# Reference_voltage.net
KiCad netlist of a schematic drawn in Altium Designer
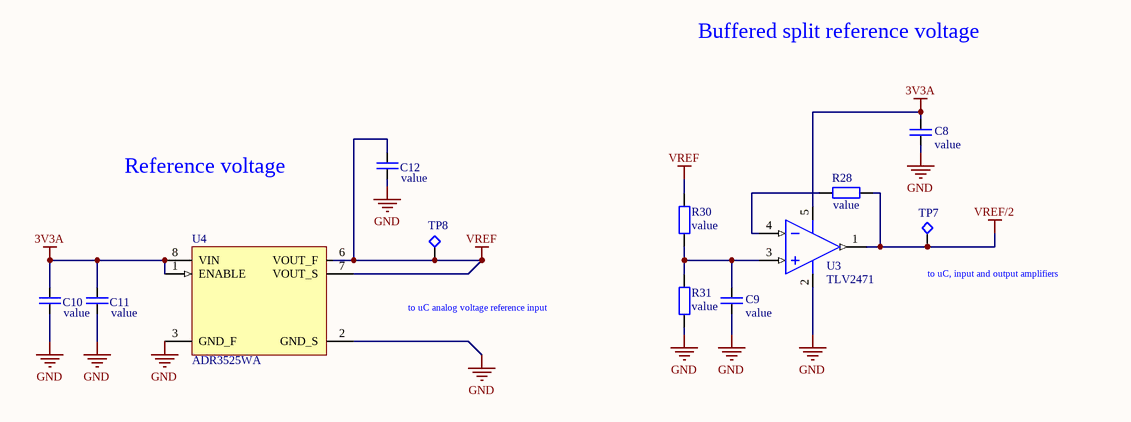
[diagram p0: Reference_voltage.SchDoc]

(export (version "E")
  (design (tool "Eeschema 10.0.6"))
  (components
    (comp (ref "C8")
      (value "value")
      (footprint "C_0603")
      (description "Generic capacitor")
      (fields (field (name "Comment") "comment"))
      (libsource (lib "DAQ") (part "Capacitor"))
    )
    (comp (ref "C9")
      (value "value")
      (footprint "C_0603")
      (description "Generic capacitor")
      (fields (field (name "Comment") "comment"))
      (libsource (lib "DAQ") (part "Capacitor"))
    )
    (comp (ref "C10")
      (value "value")
      (footprint "C_0603")
      (description "Generic capacitor")
      (fields (field (name "Comment") "comment"))
      (libsource (lib "DAQ") (part "Capacitor"))
    )
    (comp (ref "C11")
      (value "value")
      (footprint "C_0603")
      (description "Generic capacitor")
      (fields (field (name "Comment") "comment"))
      (libsource (lib "DAQ") (part "Capacitor"))
    )
    (comp (ref "C12")
      (value "value")
      (footprint "C_0603")
      (description "Generic capacitor")
      (fields (field (name "Comment") "comment"))
      (libsource (lib "DAQ") (part "Capacitor"))
    )
    (comp (ref "R28")
      (value "value")
      (footprint "R_0603")
      (description "Generic resistor")
      (fields (field (name "Comment") "comment"))
      (libsource (lib "DAQ") (part "Resistor"))
    )
    (comp (ref "R30")
      (value "value")
      (footprint "R_0603")
      (description "Generic resistor")
      (fields (field (name "Comment") "comment"))
      (libsource (lib "DAQ") (part "Resistor"))
    )
    (comp (ref "R31")
      (value "value")
      (footprint "R_0603")
      (description "Generic resistor")
      (fields (field (name "Comment") "comment"))
      (libsource (lib "DAQ") (part "Resistor"))
    )
    (comp (ref "TP7")
      (value "test point 1.5mm")
      (footprint "TP1_FULL")
      (description "Test point ,1.5mm diameter, no hole")
      (libsource (lib "DAQ") (part "Test Point"))
    )
    (comp (ref "TP8")
      (value "test point 1.5mm")
      (footprint "TP1_FULL")
      (description "Test point ,1.5mm diameter, no hole")
      (libsource (lib "DAQ") (part "Test Point"))
    )
    (comp (ref "U3")
      (value "TLV2471")
      (footprint "SOT23-5")
      (description "Single, 6-V, 2.8-MHz, RRIO operational amplifier 5-SOT-23 -40 to 125")
      (fields (field (name "MANUFACTURER") "Texas Instruments"))
      (libsource (lib "DAQ") (part "TLV2471"))
    )
    (comp (ref "U4")
      (value "ADR3525WA")
      (footprint "MSOP8")
      (description "Precision Voltage References 2.5V CMOS 8ppm/C")
      (fields (field (name "PART NUMBER") "VRX0002") (field (name "MANUFACTURER") "Analog devices"))
      (libsource (lib "DAQ") (part "ADR3525W"))
    )
  )
  (nets
    (net (code "1") (name "3V3A") (class "Default")
      (node (ref "C10") (pin "1") (pinfunction "1_1") (pintype "passive"))
      (node (ref "C11") (pin "1") (pinfunction "1_1") (pintype "passive"))
      (node (ref "C8") (pin "2") (pinfunction "2_2") (pintype "passive"))
      (node (ref "U3") (pin "5") (pinfunction "V+_5") (pintype "power_in"))
      (node (ref "U4") (pin "1") (pinfunction "ENABLE_1") (pintype "input"))
      (node (ref "U4") (pin "8") (pinfunction "VIN_8") (pintype "power_in"))
    )
    (net (code "2") (name "GND") (class "Default")
      (node (ref "C10") (pin "2") (pinfunction "2_2") (pintype "passive"))
      (node (ref "C11") (pin "2") (pinfunction "2_2") (pintype "passive"))
      (node (ref "C12") (pin "2") (pinfunction "2_2") (pintype "passive"))
      (node (ref "C8") (pin "1") (pinfunction "1_1") (pintype "passive"))
      (node (ref "C9") (pin "2") (pinfunction "2_2") (pintype "passive"))
      (node (ref "R31") (pin "1") (pintype "passive"))
      (node (ref "U3") (pin "2") (pinfunction "V-_2") (pintype "power_in"))
      (node (ref "U4") (pin "2") (pinfunction "GND_S_2") (pintype "power_in"))
      (node (ref "U4") (pin "3") (pinfunction "GND_F_3") (pintype "power_in"))
    )
    (net (code "3") (name "Net-(U3-+IN_A)") (class "Default")
      (node (ref "C9") (pin "1") (pinfunction "1_1") (pintype "passive"))
      (node (ref "R30") (pin "1") (pintype "passive"))
      (node (ref "R31") (pin "2") (pintype "passive"))
      (node (ref "U3") (pin "3") (pinfunction "+IN_A_3") (pintype "input"))
    )
    (net (code "4") (name "Net-(U3--IN_A)") (class "Default")
      (node (ref "R28") (pin "1") (pintype "passive"))
      (node (ref "U3") (pin "4") (pinfunction "-IN_A_4") (pintype "input"))
    )
    (net (code "5") (name "VREF") (class "Default")
      (node (ref "C12") (pin "1") (pinfunction "1_1") (pintype "passive"))
      (node (ref "R30") (pin "2") (pintype "passive"))
      (node (ref "TP8") (pin "1") (pinfunction "1_1") (pintype "passive"))
      (node (ref "U4") (pin "6") (pinfunction "VOUT_F_6") (pintype "power_in"))
      (node (ref "U4") (pin "7") (pinfunction "VOUT_S_7") (pintype "power_in"))
    )
    (net (code "6") (name "VREF{slash}2") (class "Default")
      (node (ref "R28") (pin "2") (pintype "passive"))
      (node (ref "TP7") (pin "1") (pinfunction "1_1") (pintype "passive"))
      (node (ref "U3") (pin "1") (pinfunction "OUT_A_1") (pintype "output"))
    )
  )
)
